# weatherstation.net
KiCad netlist of a schematic drawn in Altium Designer
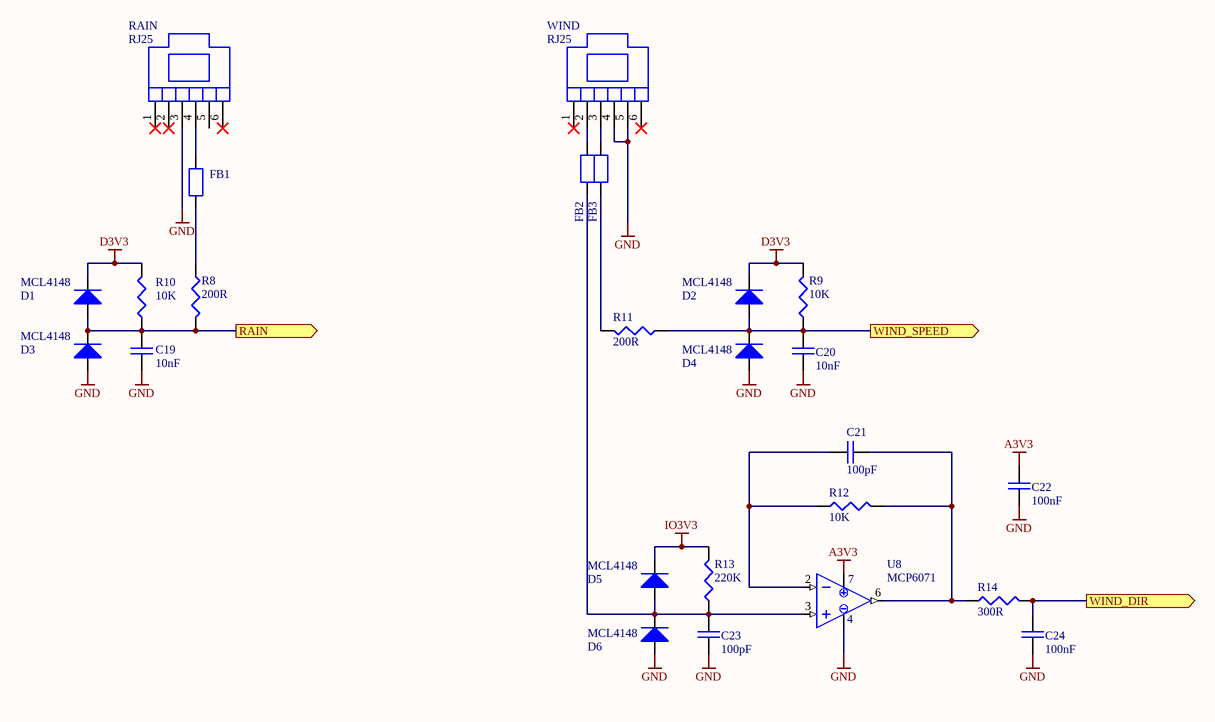
[diagram p0: weatherstation.SchDoc]

(export (version "E")
  (design (tool "Eeschema 10.0.6"))
  (components
    (comp (ref "C19")
      (value "10nF")
      (footprint "0603")
      (description "Capacitor")
      (fields (field (name "OWNER") "Nuno Brum"))
      (libsource (lib "Alcetronics_Devices") (part "CAP"))
    )
    (comp (ref "C20")
      (value "10nF")
      (footprint "0603")
      (description "Capacitor")
      (fields (field (name "OWNER") "Nuno Brum"))
      (libsource (lib "Alcetronics_Devices") (part "CAP"))
    )
    (comp (ref "C21")
      (value "100pF")
      (footprint "0603")
      (description "Capacitor")
      (fields (field (name "OWNER") "Nuno Brum"))
      (libsource (lib "Alcetronics_Devices") (part "CAP"))
    )
    (comp (ref "C22")
      (value "100nF")
      (footprint "0603")
      (description "Capacitor")
      (fields (field (name "OWNER") "Nuno Brum"))
      (libsource (lib "Alcetronics_Devices") (part "CAP"))
    )
    (comp (ref "C23")
      (value "100pF")
      (footprint "0603")
      (description "Capacitor")
      (fields (field (name "OWNER") "Nuno Brum"))
      (libsource (lib "Alcetronics_Devices") (part "CAP"))
    )
    (comp (ref "C24")
      (value "100nF")
      (footprint "0603")
      (description "Capacitor")
      (fields (field (name "OWNER") "Nuno Brum"))
      (libsource (lib "Alcetronics_Devices") (part "CAP"))
    )
    (comp (ref "D1")
      (value "MCL4148")
      (footprint "0805@DIODE")
      (description "Vishay Standard Avalanche Sinterglass Diode")
      (fields (field (name "OWNER") "Nuno Brum"))
      (libsource (lib "Alcetronics_Devices") (part "Diode"))
    )
    (comp (ref "D2")
      (value "MCL4148")
      (footprint "0805@DIODE")
      (description "Vishay Standard Avalanche Sinterglass Diode")
      (fields (field (name "OWNER") "Nuno Brum"))
      (libsource (lib "Alcetronics_Devices") (part "Diode"))
    )
    (comp (ref "D3")
      (value "MCL4148")
      (footprint "0805@DIODE")
      (description "Vishay Standard Avalanche Sinterglass Diode")
      (fields (field (name "OWNER") "Nuno Brum"))
      (libsource (lib "Alcetronics_Devices") (part "Diode"))
    )
    (comp (ref "D4")
      (value "MCL4148")
      (footprint "0805@DIODE")
      (description "Vishay Standard Avalanche Sinterglass Diode")
      (fields (field (name "OWNER") "Nuno Brum"))
      (libsource (lib "Alcetronics_Devices") (part "Diode"))
    )
    (comp (ref "D5")
      (value "MCL4148")
      (footprint "0805@DIODE")
      (description "Vishay Standard Avalanche Sinterglass Diode")
      (fields (field (name "OWNER") "Nuno Brum"))
      (libsource (lib "Alcetronics_Devices") (part "Diode"))
    )
    (comp (ref "D6")
      (value "MCL4148")
      (footprint "0805@DIODE")
      (description "Vishay Standard Avalanche Sinterglass Diode")
      (fields (field (name "OWNER") "Nuno Brum"))
      (libsource (lib "Alcetronics_Devices") (part "Diode"))
    )
    (comp (ref "FB1")
      (value "150Z_100MHz")
      (footprint "0805")
      (description "Ferrite bead")
      (fields (field (name "OWNER") "Sergio Pires"))
      (libsource (lib "Alcetronics_Devices") (part "FERRITE-BEAD-AXIAL"))
    )
    (comp (ref "FB2")
      (value "150Z_100MHz")
      (footprint "0805")
      (description "Ferrite bead")
      (fields (field (name "OWNER") "Sergio Pires"))
      (libsource (lib "Alcetronics_Devices") (part "FERRITE-BEAD-AXIAL"))
    )
    (comp (ref "FB3")
      (value "150Z_100MHz")
      (footprint "0805")
      (description "Ferrite bead")
      (fields (field (name "OWNER") "Sergio Pires"))
      (libsource (lib "Alcetronics_Devices") (part "FERRITE-BEAD-AXIAL"))
    )
    (comp (ref "R8")
      (value "200R")
      (footprint "0603")
      (description "Resistor")
      (fields (field (name "OWNER") "Nuno Brum"))
      (libsource (lib "Alcetronics_Devices") (part "RES"))
    )
    (comp (ref "R9")
      (value "10K")
      (footprint "0603")
      (description "Resistor")
      (fields (field (name "OWNER") "Nuno Brum"))
      (libsource (lib "Alcetronics_Devices") (part "RES"))
    )
    (comp (ref "R10")
      (value "10K")
      (footprint "0603")
      (description "Resistor")
      (fields (field (name "OWNER") "Nuno Brum"))
      (libsource (lib "Alcetronics_Devices") (part "RES"))
    )
    (comp (ref "R11")
      (value "200R")
      (footprint "0603")
      (description "Resistor")
      (fields (field (name "OWNER") "Nuno Brum"))
      (libsource (lib "Alcetronics_Devices") (part "RES"))
    )
    (comp (ref "R12")
      (value "10K")
      (footprint "0603")
      (description "Resistor")
      (fields (field (name "OWNER") "Nuno Brum"))
      (libsource (lib "Alcetronics_Devices") (part "RES"))
    )
    (comp (ref "R13")
      (value "220K")
      (footprint "0603")
      (description "Resistor")
      (fields (field (name "OWNER") "Nuno Brum"))
      (libsource (lib "Alcetronics_Devices") (part "RES"))
    )
    (comp (ref "R14")
      (value "300R")
      (footprint "0603")
      (description "Resistor")
      (fields (field (name "OWNER") "Nuno Brum"))
      (libsource (lib "Alcetronics_Devices") (part "RES"))
    )
    (comp (ref "RAIN")
      (value "RJ25")
      (footprint "RJ25")
      (description "RJ25 Connector")
      (libsource (lib "Alcetronics_EM") (part "RJ25"))
    )
    (comp (ref "U8")
      (value "MCP6071")
      (footprint "SOIC-8")
      (description "Low-Offset Opamp")
      (libsource (lib "Alcetronics_IC") (part "MCP6V26"))
    )
    (comp (ref "WIND")
      (value "RJ25")
      (footprint "RJ25")
      (description "RJ25 Connector")
      (libsource (lib "Alcetronics_EM") (part "RJ25"))
    )
  )
  (nets
    (net (code "1") (name "/RAIN") (class "Default")
      (node (ref "C19") (pin "2") (pinfunction "2_2") (pintype "passive"))
      (node (ref "D1") (pin "A") (pinfunction "A_A") (pintype "passive"))
      (node (ref "D3") (pin "K") (pinfunction "K_K") (pintype "passive"))
      (node (ref "R10") (pin "1") (pinfunction "1_1") (pintype "passive"))
      (node (ref "R8") (pin "2") (pinfunction "2_2") (pintype "passive"))
    )
    (net (code "2") (name "/WIND_DIR") (class "Default")
      (node (ref "C24") (pin "2") (pinfunction "2_2") (pintype "passive"))
      (node (ref "R14") (pin "2") (pinfunction "2_2") (pintype "passive"))
    )
    (net (code "3") (name "/WIND_SPEED") (class "Default")
      (node (ref "C20") (pin "2") (pinfunction "2_2") (pintype "passive"))
      (node (ref "D2") (pin "A") (pinfunction "A_A") (pintype "passive"))
      (node (ref "D4") (pin "K") (pinfunction "K_K") (pintype "passive"))
      (node (ref "R11") (pin "1") (pinfunction "1_1") (pintype "passive"))
      (node (ref "R9") (pin "1") (pinfunction "1_1") (pintype "passive"))
    )
    (net (code "4") (name "A3V3") (class "Default")
      (node (ref "C22") (pin "2") (pinfunction "2_2") (pintype "passive"))
      (node (ref "U8") (pin "7") (pinfunction "VDD_7") (pintype "power_in"))
    )
    (net (code "5") (name "D3V3") (class "Default")
      (node (ref "D1") (pin "K") (pinfunction "K_K") (pintype "passive"))
      (node (ref "D2") (pin "K") (pinfunction "K_K") (pintype "passive"))
      (node (ref "R10") (pin "2") (pinfunction "2_2") (pintype "passive"))
      (node (ref "R9") (pin "2") (pinfunction "2_2") (pintype "passive"))
    )
    (net (code "6") (name "GND") (class "Default")
      (node (ref "C19") (pin "1") (pinfunction "1_1") (pintype "passive"))
      (node (ref "C20") (pin "1") (pinfunction "1_1") (pintype "passive"))
      (node (ref "C22") (pin "1") (pinfunction "1_1") (pintype "passive"))
      (node (ref "C23") (pin "1") (pinfunction "1_1") (pintype "passive"))
      (node (ref "C24") (pin "1") (pinfunction "1_1") (pintype "passive"))
      (node (ref "D3") (pin "A") (pinfunction "A_A") (pintype "passive"))
      (node (ref "D4") (pin "A") (pinfunction "A_A") (pintype "passive"))
      (node (ref "D6") (pin "A") (pinfunction "A_A") (pintype "passive"))
      (node (ref "RAIN") (pin "3") (pinfunction "3_3") (pintype "passive"))
      (node (ref "U8") (pin "4") (pinfunction "VSS_4") (pintype "power_in"))
      (node (ref "WIND") (pin "4") (pinfunction "4_4") (pintype "passive"))
      (node (ref "WIND") (pin "5") (pinfunction "5_5") (pintype "passive"))
    )
    (net (code "7") (name "IO3V3") (class "Default")
      (node (ref "D5") (pin "K") (pinfunction "K_K") (pintype "passive"))
      (node (ref "R13") (pin "2") (pinfunction "2_2") (pintype "passive"))
    )
    (net (code "8") (name "Net-(FB1-Pad1)") (class "Default")
      (node (ref "FB1") (pin "1") (pinfunction "1_1") (pintype "passive"))
      (node (ref "R8") (pin "1") (pinfunction "1_1") (pintype "passive"))
    )
    (net (code "9") (name "Net-(FB1-Pad2)") (class "Default")
      (node (ref "FB1") (pin "2") (pinfunction "2_2") (pintype "passive"))
      (node (ref "RAIN") (pin "4") (pinfunction "4_4") (pintype "passive"))
    )
    (net (code "10") (name "Net-(FB2-Pad1)") (class "Default")
      (node (ref "FB2") (pin "1") (pinfunction "1_1") (pintype "passive"))
      (node (ref "WIND") (pin "2") (pinfunction "2_2") (pintype "passive"))
    )
    (net (code "11") (name "Net-(FB3-Pad1)") (class "Default")
      (node (ref "FB3") (pin "1") (pinfunction "1_1") (pintype "passive"))
      (node (ref "WIND") (pin "3") (pinfunction "3_3") (pintype "passive"))
    )
    (net (code "12") (name "Net-(FB3-Pad2)") (class "Default")
      (node (ref "FB3") (pin "2") (pinfunction "2_2") (pintype "passive"))
      (node (ref "R11") (pin "2") (pinfunction "2_2") (pintype "passive"))
    )
    (net (code "13") (name "Net-(U8-INN)") (class "Default")
      (node (ref "C21") (pin "1") (pinfunction "1_1") (pintype "passive"))
      (node (ref "R12") (pin "1") (pinfunction "1_1") (pintype "passive"))
      (node (ref "U8") (pin "2") (pinfunction "INN_2") (pintype "input"))
    )
    (net (code "14") (name "Net-(U8-INP)") (class "Default")
      (node (ref "C23") (pin "2") (pinfunction "2_2") (pintype "passive"))
      (node (ref "D5") (pin "A") (pinfunction "A_A") (pintype "passive"))
      (node (ref "D6") (pin "K") (pinfunction "K_K") (pintype "passive"))
      (node (ref "FB2") (pin "2") (pinfunction "2_2") (pintype "passive"))
      (node (ref "R13") (pin "1") (pinfunction "1_1") (pintype "passive"))
      (node (ref "U8") (pin "3") (pinfunction "INP_3") (pintype "input"))
    )
    (net (code "15") (name "Net-(U8-VOUT)") (class "Default")
      (node (ref "C21") (pin "2") (pinfunction "2_2") (pintype "passive"))
      (node (ref "R12") (pin "2") (pinfunction "2_2") (pintype "passive"))
      (node (ref "R14") (pin "1") (pinfunction "1_1") (pintype "passive"))
      (node (ref "U8") (pin "6") (pinfunction "VOUT_6") (pintype "output"))
    )
    (net (code "16") (name "unconnected-(RAIN-Pad1)") (class "Default")
      (node (ref "RAIN") (pin "1") (pinfunction "1_1") (pintype "passive+no_connect"))
    )
    (net (code "17") (name "unconnected-(RAIN-Pad2)") (class "Default")
      (node (ref "RAIN") (pin "2") (pinfunction "2_2") (pintype "passive+no_connect"))
    )
    (net (code "18") (name "unconnected-(RAIN-Pad5)") (class "Default")
      (node (ref "RAIN") (pin "5") (pinfunction "5_5") (pintype "passive"))
    )
    (net (code "19") (name "unconnected-(RAIN-Pad6)") (class "Default")
      (node (ref "RAIN") (pin "6") (pinfunction "6_6") (pintype "passive+no_connect"))
    )
    (net (code "20") (name "unconnected-(WIND-Pad1)") (class "Default")
      (node (ref "WIND") (pin "1") (pinfunction "1_1") (pintype "passive+no_connect"))
    )
    (net (code "21") (name "unconnected-(WIND-Pad6)") (class "Default")
      (node (ref "WIND") (pin "6") (pinfunction "6_6") (pintype "passive+no_connect"))
    )
  )
)
